# Battery_monitor_fix.net
KiCad netlist of a schematic drawn in EAGLE
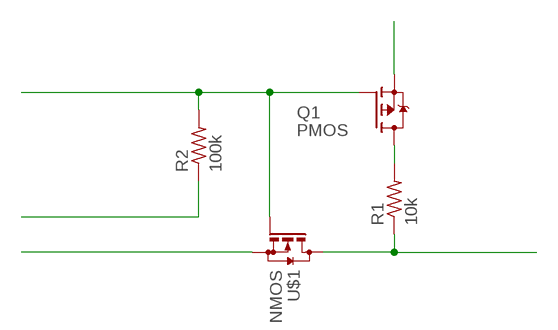
[diagram p0: schematic, sheet 1]

(export (version "E")
  (design (tool "Eeschema 10.0.6"))
  (components
    (comp (ref "Q1")
      (value "PMOS")
      (footprint "eagle-import:SC70")
      (libsource (lib "eagle-import") (part "PMOS"))
    )
    (comp (ref "R1")
      (value "10k")
      (footprint "eagle-import:0402_REAL")
      (libsource (lib "eagle-import") (part "R-US_0402_REAL"))
    )
    (comp (ref "R2")
      (value "100k")
      (footprint "eagle-import:0402_REAL")
      (libsource (lib "eagle-import") (part "R-US_0402_REAL"))
    )
    (comp (ref "U$1")
      (value "NMOS")
      (footprint "eagle-import:SC70")
      (libsource (lib "eagle-import") (part "NMOS"))
    )
  )
  (nets
    (net (code "1") (name "Net-(Q1-PadD)") (class "Default")
      (node (ref "Q1") (pin "D") (pinfunction "D_D") (pintype "passive"))
      (node (ref "R1") (pin "2") (pinfunction "2_2") (pintype "passive"))
    )
    (net (code "2") (name "Net-(Q1-PadG)") (class "Default")
      (node (ref "Q1") (pin "G") (pinfunction "G_G") (pintype "passive"))
      (node (ref "R2") (pin "2") (pinfunction "2_2") (pintype "passive"))
      (node (ref "U$1") (pin "G") (pinfunction "G_G") (pintype "passive"))
    )
    (net (code "3") (name "Net-(R1-Pad1)") (class "Default")
      (node (ref "R1") (pin "1") (pinfunction "1_1") (pintype "passive"))
      (node (ref "U$1") (pin "D") (pinfunction "D_D") (pintype "passive"))
    )
    (net (code "4") (name "unconnected-(Q1-PadS)") (class "Default")
      (node (ref "Q1") (pin "S") (pinfunction "S_S") (pintype "passive"))
    )
    (net (code "5") (name "unconnected-(R2-Pad1)") (class "Default")
      (node (ref "R2") (pin "1") (pinfunction "1_1") (pintype "passive"))
    )
    (net (code "6") (name "unconnected-(U$1-PadS)") (class "Default")
      (node (ref "U$1") (pin "S") (pinfunction "S_S") (pintype "passive"))
    )
  )
)
